# STorM32_Micro_UsbPower_v02_micro.net
KiCad netlist of a schematic drawn in EAGLE
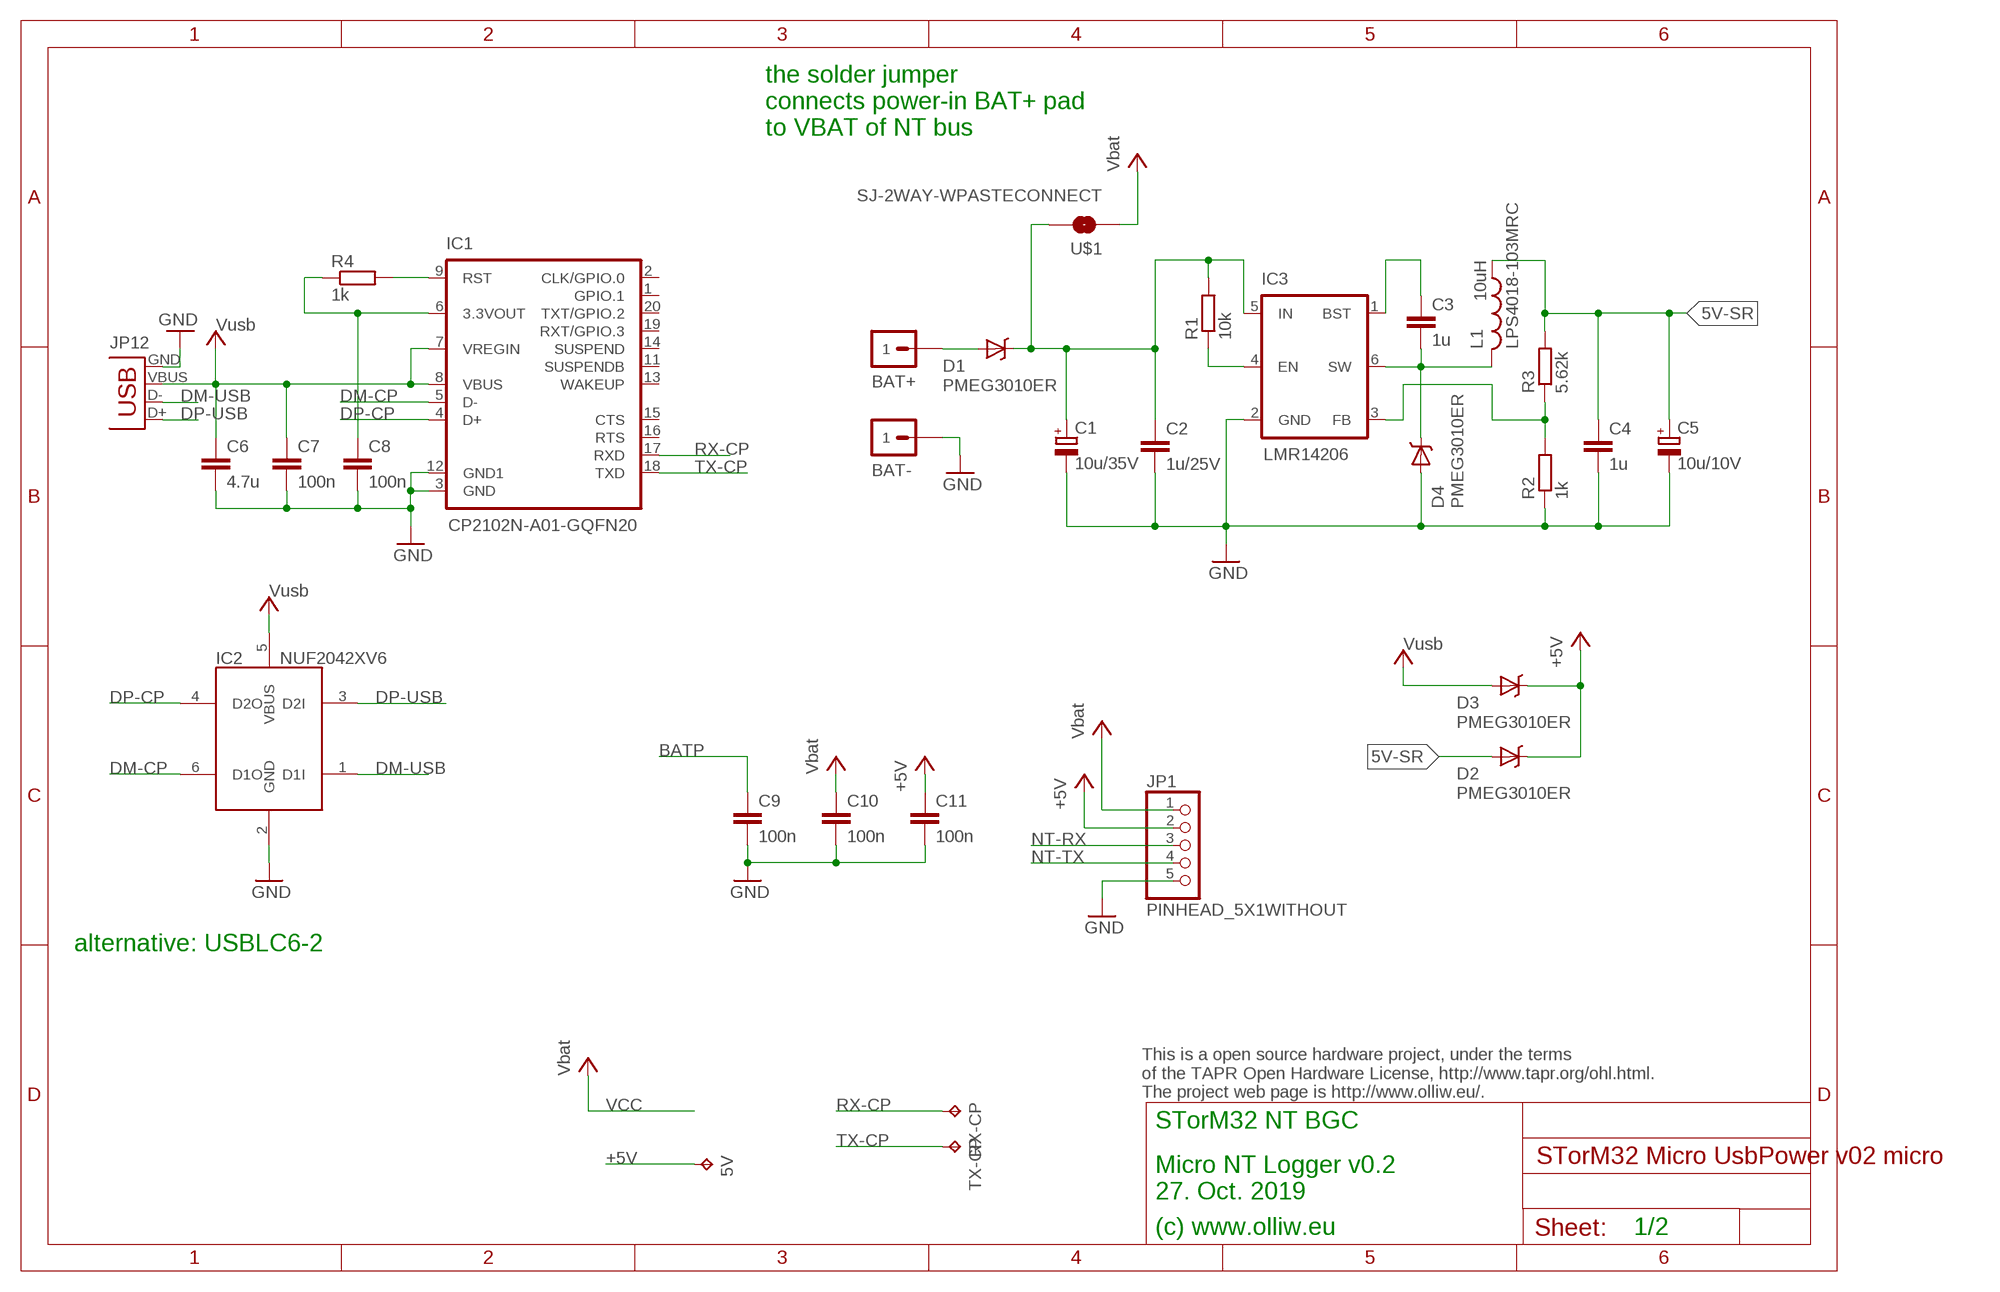
[diagram p0: schematic, sheet 1]

(export (version "E")
  (design (tool "Eeschema 10.0.6"))
  (components
    (comp (ref "5V")
      (value "TPB1,27")
      (footprint "eagle-import:B1,27")
      (libsource (lib "eagle-import") (part "TPB1,27"))
    )
    (comp (ref "BAT+")
      (value "M1X1")
      (footprint "eagle-import:1X1_WITHOUT")
      (libsource (lib "eagle-import") (part "M1X1"))
    )
    (comp (ref "BAT-")
      (value "M1X1")
      (footprint "eagle-import:1X1_WITHOUT")
      (libsource (lib "eagle-import") (part "M1X1"))
    )
    (comp (ref "C1")
      (value "10u/35V")
      (footprint "eagle-import:SMC_B")
      (libsource (lib "eagle-import") (part "CPOL-EUSMCB"))
    )
    (comp (ref "C2")
      (value "1u/25V")
      (footprint "eagle-import:C0603")
      (libsource (lib "eagle-import") (part "C-EUC0603"))
    )
    (comp (ref "C3")
      (value "1u")
      (footprint "eagle-import:C0603")
      (libsource (lib "eagle-import") (part "C-EUC0603"))
    )
    (comp (ref "C4")
      (value "1u")
      (footprint "eagle-import:C0603")
      (libsource (lib "eagle-import") (part "C-EUC0603"))
    )
    (comp (ref "C5")
      (value "10u/10V")
      (footprint "eagle-import:SMC_A")
      (libsource (lib "eagle-import") (part "CPOL-EUSMCA"))
    )
    (comp (ref "C6")
      (value "4.7u")
      (footprint "eagle-import:C0603")
      (libsource (lib "eagle-import") (part "C-EUC0603"))
    )
    (comp (ref "C7")
      (value "100n")
      (footprint "eagle-import:C0402")
      (libsource (lib "eagle-import") (part "C-EUC0402"))
    )
    (comp (ref "C8")
      (value "100n")
      (footprint "eagle-import:C0402")
      (libsource (lib "eagle-import") (part "C-EUC0402"))
    )
    (comp (ref "C9")
      (value "100n")
      (footprint "eagle-import:C0603")
      (libsource (lib "eagle-import") (part "C-EUC0603"))
    )
    (comp (ref "C10")
      (value "100n")
      (footprint "eagle-import:C0603")
      (libsource (lib "eagle-import") (part "C-EUC0603"))
    )
    (comp (ref "C11")
      (value "100n")
      (footprint "eagle-import:C0402")
      (libsource (lib "eagle-import") (part "C-EUC0402"))
    )
    (comp (ref "D1")
      (value "PMEG3010ER")
      (footprint "eagle-import:SOD123W-DIODE")
      (libsource (lib "eagle-import") (part "DIODE-SCHOTTKYSOD123-W"))
    )
    (comp (ref "D2")
      (value "PMEG3010ER")
      (footprint "eagle-import:SOD123W-DIODE")
      (libsource (lib "eagle-import") (part "DIODE-SCHOTTKYSOD123-W"))
    )
    (comp (ref "D3")
      (value "PMEG3010ER")
      (footprint "eagle-import:SOD123W-DIODE")
      (libsource (lib "eagle-import") (part "DIODE-SCHOTTKYSOD123-W"))
    )
    (comp (ref "D4")
      (value "PMEG3010ER")
      (footprint "eagle-import:SOD123W-DIODE")
      (libsource (lib "eagle-import") (part "DIODE-SCHOTTKYSOD123-W"))
    )
    (comp (ref "IC1")
      (value "CP2102N-A01-GQFN20")
      (footprint "eagle-import:QFN20-CP2102N")
      (libsource (lib "eagle-import") (part "CP2102N-QFN20"))
    )
    (comp (ref "IC2")
      (value "NUF2042XV6")
      (footprint "eagle-import:SOT563-6")
      (libsource (lib "eagle-import") (part "NUF2042XV6"))
    )
    (comp (ref "IC3")
      (value "LMR14206")
      (footprint "eagle-import:SOT23-6")
      (libsource (lib "eagle-import") (part "MP2359"))
    )
    (comp (ref "JP1")
      (value "PINHEAD_5X1WITHOUT")
      (footprint "eagle-import:PINHEAD_5X1_WO")
      (libsource (lib "eagle-import") (part "PINHEAD_5X1WITHOUT"))
    )
    (comp (ref "L1")
      (value "LPS4018-103MRC")
      (footprint "eagle-import:L4X4")
      (libsource (lib "eagle-import") (part "L"))
    )
    (comp (ref "R1")
      (value "10k")
      (footprint "eagle-import:R0402")
      (libsource (lib "eagle-import") (part "R-EU_R0402"))
    )
    (comp (ref "R2")
      (value "1k")
      (footprint "eagle-import:R0402")
      (libsource (lib "eagle-import") (part "R-EU_R0402"))
    )
    (comp (ref "R3")
      (value "5.62k")
      (footprint "eagle-import:R0402")
      (libsource (lib "eagle-import") (part "R-EU_R0402"))
    )
    (comp (ref "R4")
      (value "1k")
      (footprint "eagle-import:R0402")
      (libsource (lib "eagle-import") (part "R-EU_R0402"))
    )
    (comp (ref "RX-CP")
      (value "TPB1,27")
      (footprint "eagle-import:B1,27")
      (libsource (lib "eagle-import") (part "TPB1,27"))
    )
    (comp (ref "TX-CP")
      (value "TPB1,27")
      (footprint "eagle-import:B1,27")
      (libsource (lib "eagle-import") (part "TPB1,27"))
    )
    (comp (ref "U$1")
      (value "SJ-2WAY-WPASTECONNECT")
      (footprint "eagle-import:SJ-2WAY-BIG-WPASTEC")
      (libsource (lib "eagle-import") (part "SJ-2WAY-WPASTECONNECT"))
    )
    (comp (ref "USB")
      (value "Amphenol 10118192-0001LF")
      (footprint "eagle-import:USB-MICROB")
      (libsource (lib "eagle-import") (part "USB-MICROB"))
    )
  )
  (nets
    (net (code "1") (name "+5V") (class "Default")
      (node (ref "5V") (pin "TP") (pinfunction "TP_TP") (pintype "input"))
      (node (ref "C11") (pin "1") (pinfunction "1_1") (pintype "passive"))
      (node (ref "D2") (pin "C") (pinfunction "C_C") (pintype "passive"))
      (node (ref "D3") (pin "C") (pinfunction "C_C") (pintype "passive"))
      (node (ref "JP1") (pin "2") (pinfunction "2_2") (pintype "passive"))
    )
    (net (code "2") (name "/BATP") (class "Default")
      (node (ref "BAT+") (pin "1") (pinfunction "1_1") (pintype "passive"))
      (node (ref "C9") (pin "1") (pinfunction "1_1") (pintype "passive"))
      (node (ref "D1") (pin "A") (pinfunction "A_A") (pintype "passive"))
    )
    (net (code "3") (name "/DM-CP") (class "Default")
      (node (ref "IC1") (pin "5") (pinfunction "D-_5") (pintype "bidirectional"))
      (node (ref "IC2") (pin "6") (pinfunction "D1O_6") (pintype "bidirectional"))
    )
    (net (code "4") (name "/DM-USB") (class "Default")
      (node (ref "IC2") (pin "1") (pinfunction "D1I_1") (pintype "bidirectional"))
      (node (ref "USB") (pin "D-") (pinfunction "D-_D-") (pintype "bidirectional"))
    )
    (net (code "5") (name "/DP-CP") (class "Default")
      (node (ref "IC1") (pin "4") (pinfunction "D+_4") (pintype "bidirectional"))
      (node (ref "IC2") (pin "4") (pinfunction "D2O_4") (pintype "bidirectional"))
    )
    (net (code "6") (name "/DP-USB") (class "Default")
      (node (ref "IC2") (pin "3") (pinfunction "D2I_3") (pintype "bidirectional"))
      (node (ref "USB") (pin "D+") (pinfunction "D+_D+") (pintype "bidirectional"))
    )
    (net (code "7") (name "/NT-RX") (class "Default")
      (node (ref "JP1") (pin "3") (pinfunction "3_3") (pintype "passive"))
    )
    (net (code "8") (name "/NT-TX") (class "Default")
      (node (ref "JP1") (pin "4") (pinfunction "4_4") (pintype "passive"))
    )
    (net (code "9") (name "/RX-CP") (class "Default")
      (node (ref "IC1") (pin "17") (pinfunction "RXD_17") (pintype "input"))
      (node (ref "RX-CP") (pin "TP") (pinfunction "TP_TP") (pintype "input"))
    )
    (net (code "10") (name "/TX-CP") (class "Default")
      (node (ref "IC1") (pin "18") (pinfunction "TXD_18") (pintype "output"))
      (node (ref "TX-CP") (pin "TP") (pinfunction "TP_TP") (pintype "input"))
    )
    (net (code "11") (name "5V-SR") (class "Default")
      (node (ref "C4") (pin "1") (pinfunction "1_1") (pintype "passive"))
      (node (ref "C5") (pin "+") (pinfunction "+_+") (pintype "passive"))
      (node (ref "D2") (pin "A") (pinfunction "A_A") (pintype "passive"))
      (node (ref "L1") (pin "1") (pinfunction "1_1") (pintype "passive"))
      (node (ref "R3") (pin "2") (pinfunction "2_2") (pintype "passive"))
    )
    (net (code "12") (name "GND") (class "Default")
      (node (ref "BAT-") (pin "1") (pinfunction "1_1") (pintype "passive"))
      (node (ref "C1") (pin "-") (pinfunction "-_-") (pintype "passive"))
      (node (ref "C10") (pin "2") (pinfunction "2_2") (pintype "passive"))
      (node (ref "C11") (pin "2") (pinfunction "2_2") (pintype "passive"))
      (node (ref "C2") (pin "2") (pinfunction "2_2") (pintype "passive"))
      (node (ref "C4") (pin "2") (pinfunction "2_2") (pintype "passive"))
      (node (ref "C5") (pin "-") (pinfunction "-_-") (pintype "passive"))
      (node (ref "C6") (pin "2") (pinfunction "2_2") (pintype "passive"))
      (node (ref "C7") (pin "2") (pinfunction "2_2") (pintype "passive"))
      (node (ref "C8") (pin "2") (pinfunction "2_2") (pintype "passive"))
      (node (ref "C9") (pin "2") (pinfunction "2_2") (pintype "passive"))
      (node (ref "D4") (pin "A") (pinfunction "A_A") (pintype "passive"))
      (node (ref "IC1") (pin "12") (pinfunction "GND1_12") (pintype "power_in"))
      (node (ref "IC1") (pin "3") (pinfunction "GND_3") (pintype "power_in"))
      (node (ref "IC2") (pin "2") (pinfunction "GND_2") (pintype "bidirectional"))
      (node (ref "IC3") (pin "2") (pinfunction "GND_2") (pintype "power_in"))
      (node (ref "JP1") (pin "5") (pinfunction "5_5") (pintype "passive"))
      (node (ref "R2") (pin "1") (pinfunction "1_1") (pintype "passive"))
      (node (ref "USB") (pin "GND") (pinfunction "GND_GND") (pintype "bidirectional"))
    )
    (net (code "13") (name "Net-(IC1-3.3VOUT)") (class "Default")
      (node (ref "C8") (pin "1") (pinfunction "1_1") (pintype "passive"))
      (node (ref "IC1") (pin "6") (pinfunction "3.3VOUT_6") (pintype "power_in"))
      (node (ref "R4") (pin "1") (pinfunction "1_1") (pintype "passive"))
    )
    (net (code "14") (name "Net-(IC1-RST)") (class "Default")
      (node (ref "IC1") (pin "9") (pinfunction "RST_9") (pintype "input"))
      (node (ref "R4") (pin "2") (pinfunction "2_2") (pintype "passive"))
    )
    (net (code "15") (name "Net-(IC3-BST)") (class "Default")
      (node (ref "C3") (pin "1") (pinfunction "1_1") (pintype "passive"))
      (node (ref "IC3") (pin "1") (pinfunction "BST_1") (pintype "output"))
    )
    (net (code "16") (name "Net-(IC3-EN)") (class "Default")
      (node (ref "IC3") (pin "4") (pinfunction "EN_4") (pintype "input"))
      (node (ref "R1") (pin "1") (pinfunction "1_1") (pintype "passive"))
    )
    (net (code "17") (name "Net-(IC3-FB)") (class "Default")
      (node (ref "IC3") (pin "3") (pinfunction "FB_3") (pintype "input"))
      (node (ref "R2") (pin "2") (pinfunction "2_2") (pintype "passive"))
      (node (ref "R3") (pin "1") (pinfunction "1_1") (pintype "passive"))
    )
    (net (code "18") (name "Net-(IC3-IN)") (class "Default")
      (node (ref "C1") (pin "+") (pinfunction "+_+") (pintype "passive"))
      (node (ref "C2") (pin "1") (pinfunction "1_1") (pintype "passive"))
      (node (ref "D1") (pin "C") (pinfunction "C_C") (pintype "passive"))
      (node (ref "IC3") (pin "5") (pinfunction "IN_5") (pintype "power_in"))
      (node (ref "R1") (pin "2") (pinfunction "2_2") (pintype "passive"))
      (node (ref "U$1") (pin "2") (pinfunction "2_2") (pintype "passive"))
    )
    (net (code "19") (name "Net-(IC3-SW)") (class "Default")
      (node (ref "C3") (pin "2") (pinfunction "2_2") (pintype "passive"))
      (node (ref "D4") (pin "C") (pinfunction "C_C") (pintype "passive"))
      (node (ref "IC3") (pin "6") (pinfunction "SW_6") (pintype "output"))
      (node (ref "L1") (pin "2") (pinfunction "2_2") (pintype "passive"))
    )
    (net (code "20") (name "Vbat") (class "Default")
      (node (ref "C10") (pin "1") (pinfunction "1_1") (pintype "passive"))
      (node (ref "JP1") (pin "1") (pinfunction "1_1") (pintype "passive"))
      (node (ref "U$1") (pin "1") (pinfunction "1_1") (pintype "passive"))
    )
    (net (code "21") (name "Vusb") (class "Default")
      (node (ref "C6") (pin "1") (pinfunction "1_1") (pintype "passive"))
      (node (ref "C7") (pin "1") (pinfunction "1_1") (pintype "passive"))
      (node (ref "D3") (pin "A") (pinfunction "A_A") (pintype "passive"))
      (node (ref "IC1") (pin "7") (pinfunction "VREGIN_7") (pintype "power_in"))
      (node (ref "IC1") (pin "8") (pinfunction "VBUS_8") (pintype "input"))
      (node (ref "IC2") (pin "5") (pinfunction "VBUS_5") (pintype "bidirectional"))
      (node (ref "USB") (pin "VBUS") (pinfunction "VBUS_VBUS") (pintype "bidirectional"))
    )
    (net (code "22") (name "unconnected-(IC1-CLK{slash}GPIO.0-Pad2)") (class "Default")
      (node (ref "IC1") (pin "2") (pinfunction "CLK/GPIO.0_2") (pintype "bidirectional"))
    )
    (net (code "23") (name "unconnected-(IC1-CTS-Pad15)") (class "Default")
      (node (ref "IC1") (pin "15") (pinfunction "CTS_15") (pintype "input"))
    )
    (net (code "24") (name "unconnected-(IC1-GPIO.1-Pad1)") (class "Default")
      (node (ref "IC1") (pin "1") (pinfunction "GPIO.1_1") (pintype "bidirectional"))
    )
    (net (code "25") (name "unconnected-(IC1-RTS-Pad16)") (class "Default")
      (node (ref "IC1") (pin "16") (pinfunction "RTS_16") (pintype "output"))
    )
    (net (code "26") (name "unconnected-(IC1-RXT{slash}GPIO.3-Pad19)") (class "Default")
      (node (ref "IC1") (pin "19") (pinfunction "RXT/GPIO.3_19") (pintype "bidirectional"))
    )
    (net (code "27") (name "unconnected-(IC1-SUSPEND-Pad14)") (class "Default")
      (node (ref "IC1") (pin "14") (pinfunction "SUSPEND_14") (pintype "output"))
    )
    (net (code "28") (name "unconnected-(IC1-SUSPENDB-Pad11)") (class "Default")
      (node (ref "IC1") (pin "11") (pinfunction "SUSPENDB_11") (pintype "output"))
    )
    (net (code "29") (name "unconnected-(IC1-TXT{slash}GPIO.2-Pad20)") (class "Default")
      (node (ref "IC1") (pin "20") (pinfunction "TXT/GPIO.2_20") (pintype "bidirectional"))
    )
    (net (code "30") (name "unconnected-(IC1-WAKEUP-Pad13)") (class "Default")
      (node (ref "IC1") (pin "13") (pinfunction "WAKEUP_13") (pintype "input"))
    )
  )
)
